# MySen_singleLED_EasyEDA_Schematic.net
KiCad netlist of a schematic drawn in EasyEDA
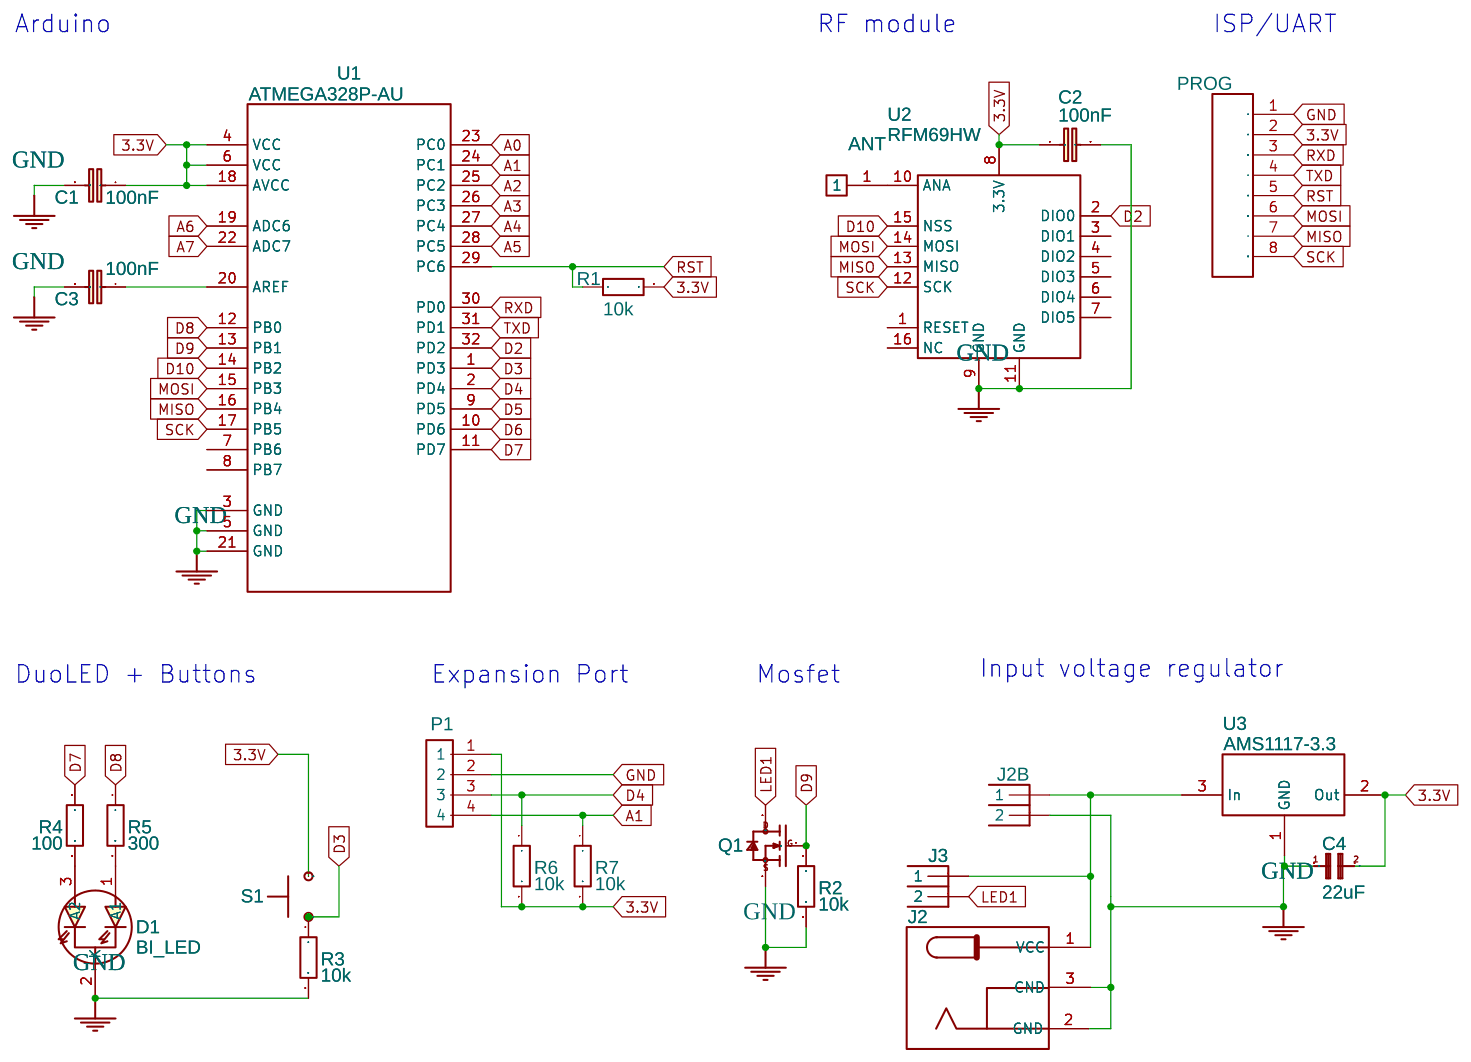
[diagram p0: schematic sheet]

(export (version "E")
  (design (tool "Eeschema 10.0.6"))
  (components
    (comp (ref "ANT") (value "1-S-PAD") (libsource (lib "") (part "Unknown_505_170")))
    (comp (ref "C1")
      (value "100nF")
      (fields (field (name "BOM_Manufacturer Part") "?"))
      (libsource (lib "") (part "Unknown_130_170"))
    )
    (comp (ref "C2")
      (value "100nF")
      (fields (field (name "BOM_Manufacturer Part") "?"))
      (libsource (lib "") (part "Unknown_620_150"))
    )
    (comp (ref "C3")
      (value "100nF")
      (fields (field (name "BOM_Manufacturer Part") "?"))
      (libsource (lib "") (part "Unknown_130_220"))
    )
    (comp (ref "C4")
      (value "22uF")
      (fields (field (name "BOM_Manufacturer Part") "?"))
      (libsource (lib "") (part "Unknown_745_505"))
    )
    (comp (ref "D1")
      (value "BI_LED")
      (fields (field (name "BOM_Manufacturer Part") "?"))
      (libsource (lib "") (part "Unknown_135_535"))
    )
    (comp (ref "J2")
      (value "DC Barrel Jack")
      (fields (field (name "BOM_Manufacturer Part") "?"))
      (libsource (lib "") (part "Unknown_535_535"))
    )
    (comp (ref "J2B") (value "Terminal 2Pol 5,08mm") (libsource (lib "") (part "Unknown_595_485")))
    (comp (ref "J3") (value "Terminal 2Pol 5,08mm") (libsource (lib "") (part "Unknown_555_525")))
    (comp (ref "P1")
      (value "4pin default")
      (fields (field (name "BOM_Manufacturer Part") "?"))
      (libsource (lib "") (part "Unknown_310_460"))
    )
    (comp (ref "PROG")
      (value "Header 2pin")
      (fields (field (name "BOM_Manufacturer Part") "?"))
      (libsource (lib "") (part "Unknown_705_125"))
    )
    (comp (ref "Q1")
      (value "IRLML2502TRPBF")
      (fields (field (name "BOM_Manufacturer Part") "?"))
      (libsource (lib "") (part "Unknown_465_495"))
    )
    (comp (ref "R1")
      (value "10k")
      (fields (field (name "BOM_Manufacturer Part") "1206 J000T5E"))
      (libsource (lib "") (part "Unknown_395_220"))
    )
    (comp (ref "R2")
      (value "10k")
      (fields (field (name "BOM_Manufacturer Part") "1206 J000T5E"))
      (libsource (lib "") (part "Unknown_485_515"))
    )
    (comp (ref "R3")
      (value "10k")
      (fields (field (name "BOM_Manufacturer Part") "1206 J000T5E"))
      (libsource (lib "") (part "Unknown_240_550"))
    )
    (comp (ref "R4")
      (value "100")
      (fields (field (name "BOM_Manufacturer Part") "1206 J000T5E"))
      (libsource (lib "") (part "Unknown_125_485"))
    )
    (comp (ref "R5")
      (value "300")
      (fields (field (name "BOM_Manufacturer Part") "1206 J000T5E"))
      (libsource (lib "") (part "Unknown_145_485"))
    )
    (comp (ref "R6")
      (value "10k")
      (fields (field (name "BOM_Manufacturer Part") "1206 J000T5E"))
      (libsource (lib "") (part "Unknown_345_505"))
    )
    (comp (ref "R7")
      (value "10k")
      (fields (field (name "BOM_Manufacturer Part") "1206 J000T5E"))
      (libsource (lib "") (part "Unknown_375_505"))
    )
    (comp (ref "S1") (value "Momentary Switch Open") (libsource (lib "") (part "Unknown_240_520")))
    (comp (ref "U1") (value "ATMEGA328P-AU") (libsource (lib "") (part "Unknown_260_240")))
    (comp (ref "U2")
      (value "RFM69HW")
      (fields (field (name "BOM_Manufacturer Part") "?"))
      (libsource (lib "") (part "Unknown_580_185"))
    )
    (comp (ref "U3") (value "AMS1117-3.3") (libsource (lib "") (part "Unknown_720_470")))
  )
  (nets
    (net (code "1") (name "3.3V") (class "Default")
      (node (ref "C1") (pin "1") (pinfunction "1_1") (pintype "unspecified"))
      (node (ref "C2") (pin "1") (pinfunction "1_1") (pintype "unspecified"))
      (node (ref "C4") (pin "2") (pinfunction "2_2") (pintype "unspecified"))
      (node (ref "P1") (pin "1") (pinfunction "1_1") (pintype "unspecified"))
      (node (ref "PROG") (pin "2") (pinfunction "2_2") (pintype "unspecified"))
      (node (ref "R1") (pin "2") (pinfunction "2_2") (pintype "input"))
      (node (ref "R6") (pin "2") (pinfunction "2_2") (pintype "input"))
      (node (ref "R7") (pin "2") (pinfunction "2_2") (pintype "input"))
      (node (ref "S1") (pin "3") (pinfunction "2_3") (pintype "unspecified"))
      (node (ref "U1") (pin "18") (pinfunction "AVCC_18") (pintype "passive"))
      (node (ref "U1") (pin "4") (pinfunction "VCC_4") (pintype "passive"))
      (node (ref "U1") (pin "6") (pinfunction "VCC_6") (pintype "passive"))
      (node (ref "U2") (pin "8") (pinfunction "3.3V_8") (pintype "passive"))
      (node (ref "U3") (pin "2") (pinfunction "Out_2") (pintype "unspecified"))
    )
    (net (code "2") (name "A0") (class "Default")
      (node (ref "U1") (pin "23") (pinfunction "PC0_23") (pintype "unspecified"))
    )
    (net (code "3") (name "A1") (class "Default")
      (node (ref "P1") (pin "4") (pinfunction "4_4") (pintype "unspecified"))
      (node (ref "R7") (pin "1") (pinfunction "1_1") (pintype "input"))
      (node (ref "U1") (pin "24") (pinfunction "PC1_24") (pintype "unspecified"))
    )
    (net (code "4") (name "A2") (class "Default")
      (node (ref "U1") (pin "25") (pinfunction "PC2_25") (pintype "unspecified"))
    )
    (net (code "5") (name "A3") (class "Default")
      (node (ref "U1") (pin "26") (pinfunction "PC3_26") (pintype "unspecified"))
    )
    (net (code "6") (name "A4") (class "Default")
      (node (ref "U1") (pin "27") (pinfunction "PC4_27") (pintype "unspecified"))
    )
    (net (code "7") (name "A5") (class "Default")
      (node (ref "U1") (pin "28") (pinfunction "PC5_28") (pintype "unspecified"))
    )
    (net (code "8") (name "A6") (class "Default")
      (node (ref "U1") (pin "19") (pinfunction "ADC6_19") (pintype "input"))
    )
    (net (code "9") (name "A7") (class "Default")
      (node (ref "U1") (pin "22") (pinfunction "ADC7_22") (pintype "input"))
    )
    (net (code "10") (name "D2") (class "Default")
      (node (ref "U1") (pin "32") (pinfunction "PD2_32") (pintype "unspecified"))
      (node (ref "U2") (pin "2") (pinfunction "DIO0_2") (pintype "bidirectional"))
    )
    (net (code "11") (name "D3") (class "Default")
      (node (ref "R3") (pin "1") (pinfunction "1_1") (pintype "input"))
      (node (ref "S1") (pin "1") (pinfunction "1_1") (pintype "unspecified"))
      (node (ref "U1") (pin "1") (pinfunction "PD3_1") (pintype "unspecified"))
    )
    (net (code "12") (name "D4") (class "Default")
      (node (ref "P1") (pin "3") (pinfunction "3_3") (pintype "unspecified"))
      (node (ref "R6") (pin "1") (pinfunction "1_1") (pintype "input"))
      (node (ref "U1") (pin "2") (pinfunction "PD4_2") (pintype "unspecified"))
    )
    (net (code "13") (name "D5") (class "Default")
      (node (ref "U1") (pin "9") (pinfunction "PD5_9") (pintype "unspecified"))
    )
    (net (code "14") (name "D6") (class "Default")
      (node (ref "U1") (pin "10") (pinfunction "PD6_10") (pintype "unspecified"))
    )
    (net (code "15") (name "D7") (class "Default")
      (node (ref "R4") (pin "1") (pinfunction "1_1") (pintype "input"))
      (node (ref "U1") (pin "11") (pinfunction "PD7_11") (pintype "unspecified"))
    )
    (net (code "16") (name "D8") (class "Default")
      (node (ref "R5") (pin "1") (pinfunction "1_1") (pintype "input"))
      (node (ref "U1") (pin "12") (pinfunction "PB0_12") (pintype "unspecified"))
    )
    (net (code "17") (name "D9") (class "Default")
      (node (ref "Q1") (pin "1") (pinfunction "G_1") (pintype "unspecified"))
      (node (ref "R2") (pin "1") (pinfunction "1_1") (pintype "input"))
      (node (ref "U1") (pin "13") (pinfunction "PB1_13") (pintype "unspecified"))
    )
    (net (code "18") (name "D10") (class "Default")
      (node (ref "U1") (pin "14") (pinfunction "PB2_14") (pintype "unspecified"))
      (node (ref "U2") (pin "15") (pinfunction "NSS_15") (pintype "input"))
    )
    (net (code "19") (name "GND") (class "Default")
      (node (ref "C1") (pin "2") (pinfunction "2_2") (pintype "unspecified"))
      (node (ref "C2") (pin "2") (pinfunction "2_2") (pintype "unspecified"))
      (node (ref "C3") (pin "2") (pinfunction "2_2") (pintype "unspecified"))
      (node (ref "C4") (pin "1") (pinfunction "1_1") (pintype "unspecified"))
      (node (ref "D1") (pin "2") (pinfunction "K_2") (pintype "input"))
      (node (ref "J2") (pin "2") (pinfunction "GND_2") (pintype "unspecified"))
      (node (ref "J2") (pin "3") (pinfunction "CND_3") (pintype "unspecified"))
      (node (ref "J2B") (pin "2") (pinfunction "2_2") (pintype "unspecified"))
      (node (ref "P1") (pin "2") (pinfunction "2_2") (pintype "unspecified"))
      (node (ref "PROG") (pin "1") (pinfunction "1_1") (pintype "unspecified"))
      (node (ref "Q1") (pin "2") (pinfunction "S_2") (pintype "unspecified"))
      (node (ref "R2") (pin "2") (pinfunction "2_2") (pintype "input"))
      (node (ref "R3") (pin "2") (pinfunction "2_2") (pintype "input"))
      (node (ref "U1") (pin "21") (pinfunction "GND_21") (pintype "unspecified"))
      (node (ref "U1") (pin "3") (pinfunction "GND_3") (pintype "unspecified"))
      (node (ref "U1") (pin "5") (pinfunction "GND_5") (pintype "unspecified"))
      (node (ref "U2") (pin "11") (pinfunction "GND_11") (pintype "passive"))
      (node (ref "U2") (pin "9") (pinfunction "GND_9") (pintype "passive"))
      (node (ref "U3") (pin "1") (pinfunction "GND_1") (pintype "unspecified"))
    )
    (net (code "20") (name "LED1") (class "Default")
      (node (ref "J3") (pin "2") (pinfunction "2_2") (pintype "unspecified"))
      (node (ref "Q1") (pin "3") (pinfunction "D_3") (pintype "unspecified"))
    )
    (net (code "21") (name "MISO") (class "Default")
      (node (ref "PROG") (pin "7") (pinfunction "7_7") (pintype "unspecified"))
      (node (ref "U1") (pin "16") (pinfunction "PB4_16") (pintype "unspecified"))
      (node (ref "U2") (pin "13") (pinfunction "MISO_13") (pintype "unspecified"))
    )
    (net (code "22") (name "MOSI") (class "Default")
      (node (ref "PROG") (pin "6") (pinfunction "6_6") (pintype "unspecified"))
      (node (ref "U1") (pin "15") (pinfunction "PB3_15") (pintype "unspecified"))
      (node (ref "U2") (pin "14") (pinfunction "MOSI_14") (pintype "input"))
    )
    (net (code "23") (name "Net-(D1-A1)") (class "Default")
      (node (ref "D1") (pin "1") (pinfunction "A1_1") (pintype "input"))
      (node (ref "R5") (pin "2") (pinfunction "2_2") (pintype "input"))
    )
    (net (code "24") (name "Net-(D1-A2)") (class "Default")
      (node (ref "D1") (pin "3") (pinfunction "A2_3") (pintype "input"))
      (node (ref "R4") (pin "2") (pinfunction "2_2") (pintype "input"))
    )
    (net (code "25") (name "Net-(J2-VCC)") (class "Default")
      (node (ref "J2") (pin "1") (pinfunction "VCC_1") (pintype "unspecified"))
      (node (ref "J2B") (pin "1") (pinfunction "1_1") (pintype "unspecified"))
      (node (ref "J3") (pin "1") (pinfunction "1_1") (pintype "unspecified"))
      (node (ref "U3") (pin "3") (pinfunction "In_3") (pintype "unspecified"))
    )
    (net (code "26") (name "Net-(U1-AREF)") (class "Default")
      (node (ref "C3") (pin "1") (pinfunction "1_1") (pintype "unspecified"))
      (node (ref "U1") (pin "20") (pinfunction "AREF_20") (pintype "input"))
    )
    (net (code "27") (name "Net-(U2-ANA)") (class "Default")
      (node (ref "ANT") (pin "1") (pinfunction "1_1") (pintype "unspecified"))
      (node (ref "U2") (pin "10") (pinfunction "ANA_10") (pintype "unspecified"))
    )
    (net (code "28") (name "RST") (class "Default")
      (node (ref "PROG") (pin "5") (pinfunction "5_5") (pintype "unspecified"))
      (node (ref "R1") (pin "1") (pinfunction "1_1") (pintype "input"))
      (node (ref "U1") (pin "29") (pinfunction "PC6_29") (pintype "unspecified"))
    )
    (net (code "29") (name "RXD") (class "Default")
      (node (ref "PROG") (pin "3") (pinfunction "3_3") (pintype "unspecified"))
      (node (ref "U1") (pin "30") (pinfunction "PD0_30") (pintype "unspecified"))
    )
    (net (code "30") (name "SCK") (class "Default")
      (node (ref "PROG") (pin "8") (pinfunction "8_8") (pintype "unspecified"))
      (node (ref "U1") (pin "17") (pinfunction "PB5_17") (pintype "unspecified"))
      (node (ref "U2") (pin "12") (pinfunction "SCK_12") (pintype "input"))
    )
    (net (code "31") (name "TXD") (class "Default")
      (node (ref "PROG") (pin "4") (pinfunction "4_4") (pintype "unspecified"))
      (node (ref "U1") (pin "31") (pinfunction "PD1_31") (pintype "unspecified"))
    )
    (net (code "32") (name "unconnected-(U1-PB6-Pad7)") (class "Default")
      (node (ref "U1") (pin "7") (pinfunction "PB6_7") (pintype "unspecified"))
    )
    (net (code "33") (name "unconnected-(U1-PB7-Pad8)") (class "Default")
      (node (ref "U1") (pin "8") (pinfunction "PB7_8") (pintype "unspecified"))
    )
    (net (code "34") (name "unconnected-(U2-DIO1-Pad3)") (class "Default")
      (node (ref "U2") (pin "3") (pinfunction "DIO1_3") (pintype "bidirectional"))
    )
    (net (code "35") (name "unconnected-(U2-DIO2-Pad4)") (class "Default")
      (node (ref "U2") (pin "4") (pinfunction "DIO2_4") (pintype "bidirectional"))
    )
    (net (code "36") (name "unconnected-(U2-DIO3-Pad5)") (class "Default")
      (node (ref "U2") (pin "5") (pinfunction "DIO3_5") (pintype "bidirectional"))
    )
    (net (code "37") (name "unconnected-(U2-DIO4-Pad6)") (class "Default")
      (node (ref "U2") (pin "6") (pinfunction "DIO4_6") (pintype "bidirectional"))
    )
    (net (code "38") (name "unconnected-(U2-DIO5-Pad7)") (class "Default")
      (node (ref "U2") (pin "7") (pinfunction "DIO5_7") (pintype "bidirectional"))
    )
    (net (code "39") (name "unconnected-(U2-NC-Pad16)") (class "Default")
      (node (ref "U2") (pin "16") (pinfunction "NC_16") (pintype "unspecified"))
    )
    (net (code "40") (name "unconnected-(U2-RESET-Pad1)") (class "Default")
      (node (ref "U2") (pin "1") (pinfunction "RESET_1") (pintype "bidirectional"))
    )
  )
)
